# SENSORS.net
KiCad netlist of a schematic drawn in Altium Designer
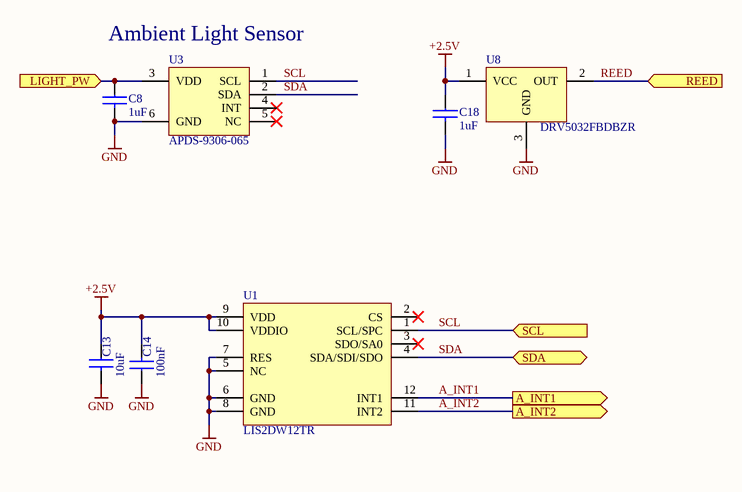
[diagram p0: SENSORS.SchDoc]

(export (version "E")
  (design (tool "Eeschema 10.0.6"))
  (components
    (comp (ref "C8")
      (value "1uF")
      (footprint "CAP0402")
      (description "CAP CER 1UF 10V 20% X5R 0402")
      (fields
        (field (name "MANUFACTURER") "Murata")
        (field (name "MANUFACTURER PART NUMBER") "GRM155R61A105ME15D")
      )
      (libsource (lib "Passive") (part "C - 1uF/0402"))
    )
    (comp (ref "C13")
      (value "10uF")
      (footprint "CAP0603")
      (description "Cap Ceramic 10uF 10V X5R 10% SMD 0603 85C Paper T/R")
      (fields
        (field (name "MANUFACTURER") "Samsung")
        (field (name "MANUFACTURER PART NUMBER") "CL10A106KP8NNNC")
      )
      (libsource (lib "Passive") (part "C - 10uF/10V"))
    )
    (comp (ref "C14")
      (value "100nF")
      (footprint "CAP0402")
      (fields
        (field (name "MANUFACTURER") "Multicomp")
        (field (name "MANUFACTURER PART NUMBER") "MC0402X104J160CT")
        (field (name "TOLERANCE") "5%")
      )
      (libsource (lib "Passive") (part "C - 100nF/0402"))
    )
    (comp (ref "C18")
      (value "1uF")
      (footprint "CAP0402")
      (description "CAP CER 1UF 10V 20% X5R 0402")
      (fields
        (field (name "MANUFACTURER") "Murata")
        (field (name "MANUFACTURER PART NUMBER") "GRM155R61A105ME15D")
      )
      (libsource (lib "Passive") (part "C - 1uF/0402"))
    )
    (comp (ref "U1")
      (value "LIS2DW12TR")
      (footprint "LGA-12")
      (description "MEMS Accelerometer, Digital, X, Y, Z, ± 2g, ± 4g, ± 8g, ± 16g, 1.62 V, 3.6 V")
      (fields
        (field (name "MANUFACTURER") "TDK InvenSense")
        (field (name "MANUFACTURER PART NUMBER") "MPU-9250")
      )
      (libsource (lib "Active") (part "SEN - LIS2DW12TR"))
    )
    (comp (ref "U3")
      (value "APDS-9306-065")
      (footprint "APDS-9306")
      (description "Ambient Light Photo Sensor, Digital I2C Output, 560nm Peak Sensitivity, 1.7V to 3.6V Supply")
      (fields
        (field (name "MANUFACTURER") "TDK InvenSense")
        (field (name "MANUFACTURER PART NUMBER") "MPU-9250")
      )
      (libsource (lib "Active") (part "SEN - APDS-9306-065"))
    )
    (comp (ref "U8")
      (value "DRV5032FBDBZR")
      (footprint "SOT23-3AL")
      (description "Board Mount Hall Effect/Magnetic Sensors LP HALL 32FBDBZR")
      (fields
        (field (name "MANUFACTURER") "TDK InvenSense")
        (field (name "MANUFACTURER PART NUMBER") "MPU-9250")
      )
      (libsource (lib "Active") (part "SEN - DRV5032FBDBZR"))
    )
  )
  (nets
    (net (code "1") (name "+2.5V") (class "Default")
      (node (ref "C13") (pin "1") (pinfunction "1_1") (pintype "passive"))
      (node (ref "C14") (pin "2") (pinfunction "2_2") (pintype "passive"))
      (node (ref "C18") (pin "1") (pinfunction "1_1") (pintype "passive"))
      (node (ref "U1") (pin "10") (pinfunction "VDDIO_10") (pintype "passive"))
      (node (ref "U1") (pin "9") (pinfunction "VDD_9") (pintype "passive"))
      (node (ref "U8") (pin "1") (pinfunction "VCC_1") (pintype "passive"))
    )
    (net (code "2") (name "/A_INT1") (class "Default")
      (node (ref "U1") (pin "12") (pinfunction "INT1_12") (pintype "passive"))
    )
    (net (code "3") (name "/A_INT2") (class "Default")
      (node (ref "U1") (pin "11") (pinfunction "INT2_11") (pintype "passive"))
    )
    (net (code "4") (name "/LIGHT_PW") (class "Default")
      (node (ref "C8") (pin "1") (pinfunction "1_1") (pintype "passive"))
      (node (ref "U3") (pin "3") (pinfunction "VDD_3") (pintype "passive"))
    )
    (net (code "5") (name "/REED") (class "Default")
      (node (ref "U8") (pin "2") (pinfunction "OUT_2") (pintype "passive"))
    )
    (net (code "6") (name "/SCL") (class "Default")
      (node (ref "U1") (pin "1") (pinfunction "SCL/SPC_1") (pintype "passive"))
      (node (ref "U3") (pin "1") (pinfunction "SCL_1") (pintype "passive"))
    )
    (net (code "7") (name "/SDA") (class "Default")
      (node (ref "U1") (pin "4") (pinfunction "SDA/SDI/SDO_4") (pintype "passive"))
      (node (ref "U3") (pin "2") (pinfunction "SDA_2") (pintype "passive"))
    )
    (net (code "8") (name "GND") (class "Default")
      (node (ref "C13") (pin "2") (pinfunction "2_2") (pintype "passive"))
      (node (ref "C14") (pin "1") (pinfunction "1_1") (pintype "passive"))
      (node (ref "C18") (pin "2") (pinfunction "2_2") (pintype "passive"))
      (node (ref "C8") (pin "2") (pinfunction "2_2") (pintype "passive"))
      (node (ref "U1") (pin "5") (pinfunction "NC_5") (pintype "passive"))
      (node (ref "U1") (pin "6") (pinfunction "GND_6") (pintype "passive"))
      (node (ref "U1") (pin "7") (pinfunction "RES_7") (pintype "passive"))
      (node (ref "U1") (pin "8") (pinfunction "GND_8") (pintype "passive"))
      (node (ref "U3") (pin "6") (pinfunction "GND_6") (pintype "passive"))
      (node (ref "U8") (pin "3") (pinfunction "GND_3") (pintype "passive"))
    )
    (net (code "9") (name "unconnected-(U1-CS-Pad2)") (class "Default")
      (node (ref "U1") (pin "2") (pinfunction "CS_2") (pintype "passive+no_connect"))
    )
    (net (code "10") (name "unconnected-(U1-SDO{slash}SA0-Pad3)") (class "Default")
      (node (ref "U1") (pin "3") (pinfunction "SDO/SA0_3") (pintype "passive+no_connect"))
    )
    (net (code "11") (name "unconnected-(U3-INT-Pad4)") (class "Default")
      (node (ref "U3") (pin "4") (pinfunction "INT_4") (pintype "passive+no_connect"))
    )
    (net (code "12") (name "unconnected-(U3-NC-Pad5)") (class "Default")
      (node (ref "U3") (pin "5") (pinfunction "NC_5") (pintype "passive+no_connect"))
    )
  )
)
